# mainv1.net
KiCad netlist of a schematic drawn in EAGLE
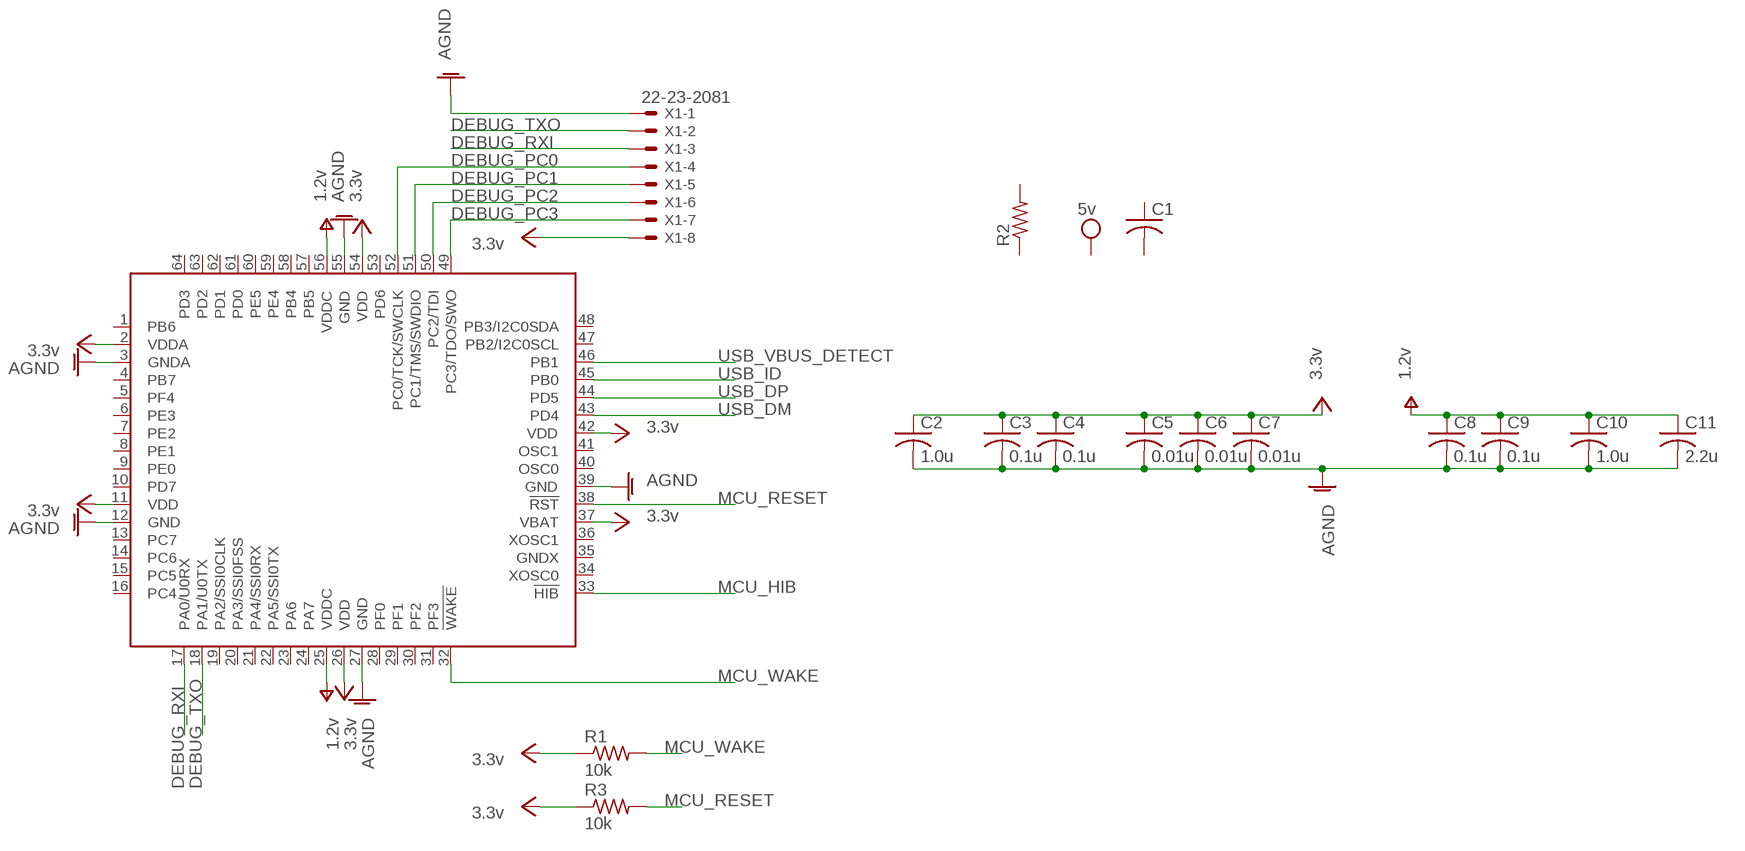
[diagram p0: schematic, sheet 1]

(export (version "E")
  (design (tool "Eeschema 10.0.6"))
  (components
    (comp (ref "C1")
      (value "C-USC0805K")
      (footprint "eagle-import:C0805K")
      (libsource (lib "eagle-import") (part "C-USC0805K"))
    )
    (comp (ref "C2")
      (value "1.0u")
      (footprint "eagle-import:C0805K")
      (libsource (lib "eagle-import") (part "C-USC0805K"))
    )
    (comp (ref "C3")
      (value "0.1u")
      (footprint "eagle-import:C0805K")
      (libsource (lib "eagle-import") (part "C-USC0805K"))
    )
    (comp (ref "C4")
      (value "0.1u")
      (footprint "eagle-import:C0805K")
      (libsource (lib "eagle-import") (part "C-USC0805K"))
    )
    (comp (ref "C5")
      (value "0.01u")
      (footprint "eagle-import:C0805K")
      (libsource (lib "eagle-import") (part "C-USC0805K"))
    )
    (comp (ref "C6")
      (value "0.01u")
      (footprint "eagle-import:C0805K")
      (libsource (lib "eagle-import") (part "C-USC0805K"))
    )
    (comp (ref "C7")
      (value "0.01u")
      (footprint "eagle-import:C0805K")
      (libsource (lib "eagle-import") (part "C-USC0805K"))
    )
    (comp (ref "C8")
      (value "0.1u")
      (footprint "eagle-import:C0805K")
      (libsource (lib "eagle-import") (part "C-USC0805K"))
    )
    (comp (ref "C9")
      (value "0.1u")
      (footprint "eagle-import:C0805K")
      (libsource (lib "eagle-import") (part "C-USC0805K"))
    )
    (comp (ref "C10")
      (value "1.0u")
      (footprint "eagle-import:C0805K")
      (libsource (lib "eagle-import") (part "C-USC0805K"))
    )
    (comp (ref "C11")
      (value "2.2u")
      (footprint "eagle-import:C0805K")
      (libsource (lib "eagle-import") (part "C-USC0805K"))
    )
    (comp (ref "IC1")
      (value "TM4C123GH6PMI")
      (footprint "eagle-import:PM_S-PQFP-G64")
      (libsource (lib "eagle-import") (part "TM4C123GH6PMI"))
    )
    (comp (ref "R1")
      (value "10k")
      (footprint "eagle-import:R0805")
      (libsource (lib "eagle-import") (part "R-US_R0805"))
    )
    (comp (ref "R2")
      (value "R-US_R0805")
      (footprint "eagle-import:R0805")
      (libsource (lib "eagle-import") (part "R-US_R0805"))
    )
    (comp (ref "R3")
      (value "10k")
      (footprint "eagle-import:R0805")
      (libsource (lib "eagle-import") (part "R-US_R0805"))
    )
    (comp (ref "X1")
      (value "22-23-2081")
      (footprint "eagle-import:22-23-2081")
      (fields (field (name "MF") "MOLEX"))
      (libsource (lib "eagle-import") (part "22-23-2081"))
    )
  )
  (nets
    (net (code "1") (name "/DEBUG_PC0") (class "Default")
      (node (ref "IC1") (pin "52") (pinfunction "PC0/TCK/SWCLK_52") (pintype "bidirectional"))
      (node (ref "X1") (pin "4") (pinfunction "S_4") (pintype "passive"))
    )
    (net (code "2") (name "/DEBUG_PC1") (class "Default")
      (node (ref "IC1") (pin "51") (pinfunction "PC1/TMS/SWDIO_51") (pintype "bidirectional"))
      (node (ref "X1") (pin "5") (pinfunction "S_5") (pintype "passive"))
    )
    (net (code "3") (name "/DEBUG_PC2") (class "Default")
      (node (ref "IC1") (pin "50") (pinfunction "PC2/TDI_50") (pintype "bidirectional"))
      (node (ref "X1") (pin "6") (pinfunction "S_6") (pintype "passive"))
    )
    (net (code "4") (name "/DEBUG_PC3") (class "Default")
      (node (ref "IC1") (pin "49") (pinfunction "PC3/TDO/SWO_49") (pintype "bidirectional"))
      (node (ref "X1") (pin "7") (pinfunction "S_7") (pintype "passive"))
    )
    (net (code "5") (name "/DEBUG_RXI") (class "Default")
      (node (ref "IC1") (pin "17") (pinfunction "PA0/U0RX_17") (pintype "bidirectional"))
      (node (ref "X1") (pin "3") (pinfunction "S_3") (pintype "passive"))
    )
    (net (code "6") (name "/DEBUG_TXO") (class "Default")
      (node (ref "IC1") (pin "18") (pinfunction "PA1/U0TX_18") (pintype "bidirectional"))
      (node (ref "X1") (pin "2") (pinfunction "S_2") (pintype "passive"))
    )
    (net (code "7") (name "/MCU_HIB") (class "Default")
      (node (ref "IC1") (pin "33") (pinfunction "~{HIB}_33") (pintype "bidirectional"))
    )
    (net (code "8") (name "/MCU_RESET") (class "Default")
      (node (ref "IC1") (pin "38") (pinfunction "~{RST}_38") (pintype "bidirectional"))
      (node (ref "R3") (pin "2") (pinfunction "2_2") (pintype "passive"))
    )
    (net (code "9") (name "/MCU_WAKE") (class "Default")
      (node (ref "IC1") (pin "32") (pinfunction "~{WAKE}_32") (pintype "bidirectional"))
      (node (ref "R1") (pin "2") (pinfunction "2_2") (pintype "passive"))
    )
    (net (code "10") (name "/USB_DM") (class "Default")
      (node (ref "IC1") (pin "43") (pinfunction "PD4_43") (pintype "bidirectional"))
    )
    (net (code "11") (name "/USB_DP") (class "Default")
      (node (ref "IC1") (pin "44") (pinfunction "PD5_44") (pintype "bidirectional"))
    )
    (net (code "12") (name "/USB_ID") (class "Default")
      (node (ref "IC1") (pin "45") (pinfunction "PB0_45") (pintype "bidirectional"))
    )
    (net (code "13") (name "/USB_VBUS_DETECT") (class "Default")
      (node (ref "IC1") (pin "46") (pinfunction "PB1_46") (pintype "bidirectional"))
    )
    (net (code "14") (name "1.2v") (class "Default")
      (node (ref "C10") (pin "1") (pinfunction "1_1") (pintype "passive"))
      (node (ref "C11") (pin "1") (pinfunction "1_1") (pintype "passive"))
      (node (ref "C8") (pin "1") (pinfunction "1_1") (pintype "passive"))
      (node (ref "C9") (pin "1") (pinfunction "1_1") (pintype "passive"))
      (node (ref "IC1") (pin "25") (pinfunction "VDDC_25") (pintype "bidirectional"))
      (node (ref "IC1") (pin "56") (pinfunction "VDDC_56") (pintype "bidirectional"))
    )
    (net (code "15") (name "3.3v") (class "Default")
      (node (ref "C2") (pin "1") (pinfunction "1_1") (pintype "passive"))
      (node (ref "C3") (pin "1") (pinfunction "1_1") (pintype "passive"))
      (node (ref "C4") (pin "1") (pinfunction "1_1") (pintype "passive"))
      (node (ref "C5") (pin "1") (pinfunction "1_1") (pintype "passive"))
      (node (ref "C6") (pin "1") (pinfunction "1_1") (pintype "passive"))
      (node (ref "C7") (pin "1") (pinfunction "1_1") (pintype "passive"))
      (node (ref "IC1") (pin "11") (pinfunction "VDD_11") (pintype "bidirectional"))
      (node (ref "IC1") (pin "2") (pinfunction "VDDA_2") (pintype "bidirectional"))
      (node (ref "IC1") (pin "26") (pinfunction "VDD_26") (pintype "bidirectional"))
      (node (ref "IC1") (pin "37") (pinfunction "VBAT_37") (pintype "bidirectional"))
      (node (ref "IC1") (pin "42") (pinfunction "VDD_42") (pintype "bidirectional"))
      (node (ref "IC1") (pin "54") (pinfunction "VDD_54") (pintype "bidirectional"))
      (node (ref "R1") (pin "1") (pinfunction "1_1") (pintype "passive"))
      (node (ref "R3") (pin "1") (pinfunction "1_1") (pintype "passive"))
      (node (ref "X1") (pin "8") (pinfunction "S_8") (pintype "passive"))
    )
    (net (code "17") (name "AGND") (class "Default")
      (node (ref "C10") (pin "2") (pinfunction "2_2") (pintype "passive"))
      (node (ref "C11") (pin "2") (pinfunction "2_2") (pintype "passive"))
      (node (ref "C2") (pin "2") (pinfunction "2_2") (pintype "passive"))
      (node (ref "C3") (pin "2") (pinfunction "2_2") (pintype "passive"))
      (node (ref "C4") (pin "2") (pinfunction "2_2") (pintype "passive"))
      (node (ref "C5") (pin "2") (pinfunction "2_2") (pintype "passive"))
      (node (ref "C6") (pin "2") (pinfunction "2_2") (pintype "passive"))
      (node (ref "C7") (pin "2") (pinfunction "2_2") (pintype "passive"))
      (node (ref "C8") (pin "2") (pinfunction "2_2") (pintype "passive"))
      (node (ref "C9") (pin "2") (pinfunction "2_2") (pintype "passive"))
      (node (ref "IC1") (pin "12") (pinfunction "GND_12") (pintype "bidirectional"))
      (node (ref "IC1") (pin "27") (pinfunction "GND_27") (pintype "bidirectional"))
      (node (ref "IC1") (pin "3") (pinfunction "GNDA_3") (pintype "bidirectional"))
      (node (ref "IC1") (pin "39") (pinfunction "GND_39") (pintype "bidirectional"))
      (node (ref "IC1") (pin "55") (pinfunction "GND_55") (pintype "bidirectional"))
      (node (ref "X1") (pin "1") (pinfunction "S_1") (pintype "passive"))
    )
    (net (code "18") (name "unconnected-(C1-Pad1)") (class "Default")
      (node (ref "C1") (pin "1") (pinfunction "1_1") (pintype "passive"))
    )
    (net (code "19") (name "unconnected-(C1-Pad2)") (class "Default")
      (node (ref "C1") (pin "2") (pinfunction "2_2") (pintype "passive"))
    )
    (net (code "20") (name "unconnected-(IC1-GNDX-Pad35)") (class "Default")
      (node (ref "IC1") (pin "35") (pinfunction "GNDX_35") (pintype "bidirectional"))
    )
    (net (code "21") (name "unconnected-(IC1-OSC0-Pad40)") (class "Default")
      (node (ref "IC1") (pin "40") (pinfunction "OSC0_40") (pintype "bidirectional"))
    )
    (net (code "22") (name "unconnected-(IC1-OSC1-Pad41)") (class "Default")
      (node (ref "IC1") (pin "41") (pinfunction "OSC1_41") (pintype "bidirectional"))
    )
    (net (code "23") (name "unconnected-(IC1-PA2{slash}SSI0CLK-Pad19)") (class "Default")
      (node (ref "IC1") (pin "19") (pinfunction "PA2/SSI0CLK_19") (pintype "bidirectional"))
    )
    (net (code "24") (name "unconnected-(IC1-PA3{slash}SSI0FSS-Pad20)") (class "Default")
      (node (ref "IC1") (pin "20") (pinfunction "PA3/SSI0FSS_20") (pintype "bidirectional"))
    )
    (net (code "25") (name "unconnected-(IC1-PA4{slash}SSI0RX-Pad21)") (class "Default")
      (node (ref "IC1") (pin "21") (pinfunction "PA4/SSI0RX_21") (pintype "bidirectional"))
    )
    (net (code "26") (name "unconnected-(IC1-PA5{slash}SSI0TX-Pad22)") (class "Default")
      (node (ref "IC1") (pin "22") (pinfunction "PA5/SSI0TX_22") (pintype "bidirectional"))
    )
    (net (code "27") (name "unconnected-(IC1-PA6-Pad23)") (class "Default")
      (node (ref "IC1") (pin "23") (pinfunction "PA6_23") (pintype "bidirectional"))
    )
    (net (code "28") (name "unconnected-(IC1-PA7-Pad24)") (class "Default")
      (node (ref "IC1") (pin "24") (pinfunction "PA7_24") (pintype "bidirectional"))
    )
    (net (code "29") (name "unconnected-(IC1-PB2{slash}I2C0SCL-Pad47)") (class "Default")
      (node (ref "IC1") (pin "47") (pinfunction "PB2/I2C0SCL_47") (pintype "bidirectional"))
    )
    (net (code "30") (name "unconnected-(IC1-PB3{slash}I2C0SDA-Pad48)") (class "Default")
      (node (ref "IC1") (pin "48") (pinfunction "PB3/I2C0SDA_48") (pintype "bidirectional"))
    )
    (net (code "31") (name "unconnected-(IC1-PB4-Pad58)") (class "Default")
      (node (ref "IC1") (pin "58") (pinfunction "PB4_58") (pintype "bidirectional"))
    )
    (net (code "32") (name "unconnected-(IC1-PB5-Pad57)") (class "Default")
      (node (ref "IC1") (pin "57") (pinfunction "PB5_57") (pintype "bidirectional"))
    )
    (net (code "33") (name "unconnected-(IC1-PB6-Pad1)") (class "Default")
      (node (ref "IC1") (pin "1") (pinfunction "PB6_1") (pintype "bidirectional"))
    )
    (net (code "34") (name "unconnected-(IC1-PB7-Pad4)") (class "Default")
      (node (ref "IC1") (pin "4") (pinfunction "PB7_4") (pintype "bidirectional"))
    )
    (net (code "35") (name "unconnected-(IC1-PC4-Pad16)") (class "Default")
      (node (ref "IC1") (pin "16") (pinfunction "PC4_16") (pintype "bidirectional"))
    )
    (net (code "36") (name "unconnected-(IC1-PC5-Pad15)") (class "Default")
      (node (ref "IC1") (pin "15") (pinfunction "PC5_15") (pintype "bidirectional"))
    )
    (net (code "37") (name "unconnected-(IC1-PC6-Pad14)") (class "Default")
      (node (ref "IC1") (pin "14") (pinfunction "PC6_14") (pintype "bidirectional"))
    )
    (net (code "38") (name "unconnected-(IC1-PC7-Pad13)") (class "Default")
      (node (ref "IC1") (pin "13") (pinfunction "PC7_13") (pintype "bidirectional"))
    )
    (net (code "39") (name "unconnected-(IC1-PD0-Pad61)") (class "Default")
      (node (ref "IC1") (pin "61") (pinfunction "PD0_61") (pintype "bidirectional"))
    )
    (net (code "40") (name "unconnected-(IC1-PD1-Pad62)") (class "Default")
      (node (ref "IC1") (pin "62") (pinfunction "PD1_62") (pintype "bidirectional"))
    )
    (net (code "41") (name "unconnected-(IC1-PD2-Pad63)") (class "Default")
      (node (ref "IC1") (pin "63") (pinfunction "PD2_63") (pintype "bidirectional"))
    )
    (net (code "42") (name "unconnected-(IC1-PD3-Pad64)") (class "Default")
      (node (ref "IC1") (pin "64") (pinfunction "PD3_64") (pintype "bidirectional"))
    )
    (net (code "43") (name "unconnected-(IC1-PD6-Pad53)") (class "Default")
      (node (ref "IC1") (pin "53") (pinfunction "PD6_53") (pintype "bidirectional"))
    )
    (net (code "44") (name "unconnected-(IC1-PD7-Pad10)") (class "Default")
      (node (ref "IC1") (pin "10") (pinfunction "PD7_10") (pintype "bidirectional"))
    )
    (net (code "45") (name "unconnected-(IC1-PE0-Pad9)") (class "Default")
      (node (ref "IC1") (pin "9") (pinfunction "PE0_9") (pintype "bidirectional"))
    )
    (net (code "46") (name "unconnected-(IC1-PE1-Pad8)") (class "Default")
      (node (ref "IC1") (pin "8") (pinfunction "PE1_8") (pintype "bidirectional"))
    )
    (net (code "47") (name "unconnected-(IC1-PE2-Pad7)") (class "Default")
      (node (ref "IC1") (pin "7") (pinfunction "PE2_7") (pintype "bidirectional"))
    )
    (net (code "48") (name "unconnected-(IC1-PE3-Pad6)") (class "Default")
      (node (ref "IC1") (pin "6") (pinfunction "PE3_6") (pintype "bidirectional"))
    )
    (net (code "49") (name "unconnected-(IC1-PE4-Pad59)") (class "Default")
      (node (ref "IC1") (pin "59") (pinfunction "PE4_59") (pintype "bidirectional"))
    )
    (net (code "50") (name "unconnected-(IC1-PE5-Pad60)") (class "Default")
      (node (ref "IC1") (pin "60") (pinfunction "PE5_60") (pintype "bidirectional"))
    )
    (net (code "51") (name "unconnected-(IC1-PF0-Pad28)") (class "Default")
      (node (ref "IC1") (pin "28") (pinfunction "PF0_28") (pintype "bidirectional"))
    )
    (net (code "52") (name "unconnected-(IC1-PF1-Pad29)") (class "Default")
      (node (ref "IC1") (pin "29") (pinfunction "PF1_29") (pintype "bidirectional"))
    )
    (net (code "53") (name "unconnected-(IC1-PF2-Pad30)") (class "Default")
      (node (ref "IC1") (pin "30") (pinfunction "PF2_30") (pintype "bidirectional"))
    )
    (net (code "54") (name "unconnected-(IC1-PF3-Pad31)") (class "Default")
      (node (ref "IC1") (pin "31") (pinfunction "PF3_31") (pintype "bidirectional"))
    )
    (net (code "55") (name "unconnected-(IC1-PF4-Pad5)") (class "Default")
      (node (ref "IC1") (pin "5") (pinfunction "PF4_5") (pintype "bidirectional"))
    )
    (net (code "56") (name "unconnected-(IC1-XOSC0-Pad34)") (class "Default")
      (node (ref "IC1") (pin "34") (pinfunction "XOSC0_34") (pintype "bidirectional"))
    )
    (net (code "57") (name "unconnected-(IC1-XOSC1-Pad36)") (class "Default")
      (node (ref "IC1") (pin "36") (pinfunction "XOSC1_36") (pintype "bidirectional"))
    )
    (net (code "58") (name "unconnected-(R2-Pad1)") (class "Default")
      (node (ref "R2") (pin "1") (pinfunction "1_1") (pintype "passive"))
    )
    (net (code "59") (name "unconnected-(R2-Pad2)") (class "Default")
      (node (ref "R2") (pin "2") (pinfunction "2_2") (pintype "passive"))
    )
  )
)
